# switchcontrol.net
KiCad netlist of a schematic drawn in EAGLE
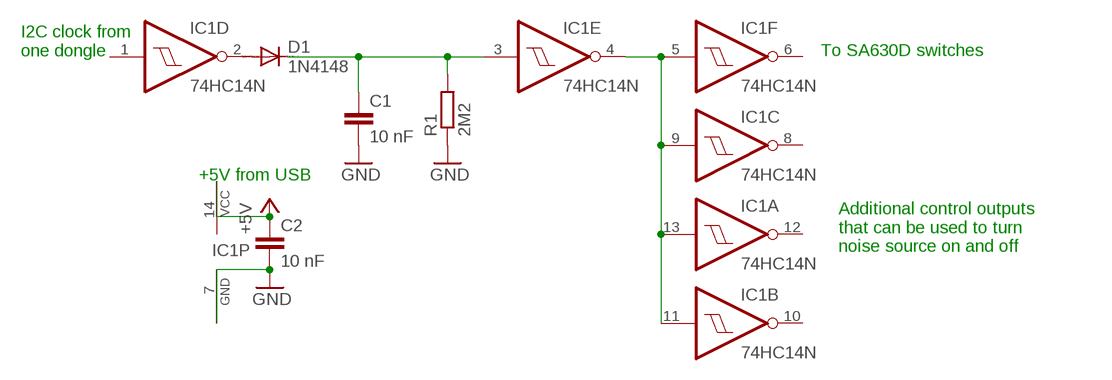
[diagram p0: schematic, sheet 1]

(export (version "E")
  (design (tool "Eeschema 10.0.6"))
  (components
    (comp (ref "C1")
      (value "10 nF")
      (footprint "eagle-import:C025-024X044")
      (libsource (lib "eagle-import") (part "C-EU025-024X044"))
    )
    (comp (ref "C2")
      (value "10 nF")
      (footprint "eagle-import:C025-024X044")
      (libsource (lib "eagle-import") (part "C-EU025-024X044"))
    )
    (comp (ref "D1")
      (value "1N4148")
      (footprint "eagle-import:DO35-10")
      (libsource (lib "eagle-import") (part "1N4148DO35-10"))
    )
    (comp (ref "IC1")
      (value "74HC14N")
      (footprint "eagle-import:DIL14")
      (libsource (lib "eagle-import") (part "7414N"))
    )
    (comp (ref "R1")
      (value "2M2")
      (footprint "eagle-import:0204_5")
      (libsource (lib "eagle-import") (part "R-EU_0204/5"))
    )
  )
  (nets
    (net (code "1") (name "+5V") (class "Default")
      (node (ref "C2") (pin "1") (pinfunction "1_1") (pintype "passive"))
      (node (ref "IC1") (pin "14") (pinfunction "VCC_14") (pintype "power_in"))
    )
    (net (code "2") (name "GND") (class "Default")
      (node (ref "C1") (pin "2") (pinfunction "2_2") (pintype "passive"))
      (node (ref "C2") (pin "2") (pinfunction "2_2") (pintype "passive"))
      (node (ref "IC1") (pin "7") (pinfunction "GND_7") (pintype "power_in"))
      (node (ref "R1") (pin "1") (pinfunction "1_1") (pintype "passive"))
    )
    (net (code "3") (name "Net-(IC1A-I)") (class "Default")
      (node (ref "IC1") (pin "11") (pinfunction "I_11") (pintype "input"))
      (node (ref "IC1") (pin "13") (pinfunction "I_13") (pintype "input"))
      (node (ref "IC1") (pin "4") (pinfunction "O_4") (pintype "output"))
      (node (ref "IC1") (pin "5") (pinfunction "I_5") (pintype "input"))
      (node (ref "IC1") (pin "9") (pinfunction "I_9") (pintype "input"))
    )
    (net (code "4") (name "Net-(IC1D-O)") (class "Default")
      (node (ref "D1") (pin "A") (pinfunction "A_A") (pintype "passive"))
      (node (ref "IC1") (pin "2") (pinfunction "O_2") (pintype "output"))
    )
    (net (code "5") (name "Net-(IC1E-I)") (class "Default")
      (node (ref "C1") (pin "1") (pinfunction "1_1") (pintype "passive"))
      (node (ref "D1") (pin "C") (pinfunction "C_C") (pintype "passive"))
      (node (ref "IC1") (pin "3") (pinfunction "I_3") (pintype "input"))
      (node (ref "R1") (pin "2") (pinfunction "2_2") (pintype "passive"))
    )
    (net (code "6") (name "unconnected-(IC1A-O-Pad12)") (class "Default")
      (node (ref "IC1") (pin "12") (pinfunction "O_12") (pintype "output"))
    )
    (net (code "7") (name "unconnected-(IC1B-O-Pad10)") (class "Default")
      (node (ref "IC1") (pin "10") (pinfunction "O_10") (pintype "output"))
    )
    (net (code "8") (name "unconnected-(IC1C-O-Pad8)") (class "Default")
      (node (ref "IC1") (pin "8") (pinfunction "O_8") (pintype "output"))
    )
    (net (code "9") (name "unconnected-(IC1D-I-Pad1)") (class "Default")
      (node (ref "IC1") (pin "1") (pinfunction "I_1") (pintype "input"))
    )
    (net (code "10") (name "unconnected-(IC1F-O-Pad6)") (class "Default")
      (node (ref "IC1") (pin "6") (pinfunction "O_6") (pintype "output"))
    )
  )
)
